# slider_pot_v0_1.net
KiCad netlist of a schematic drawn in EAGLE
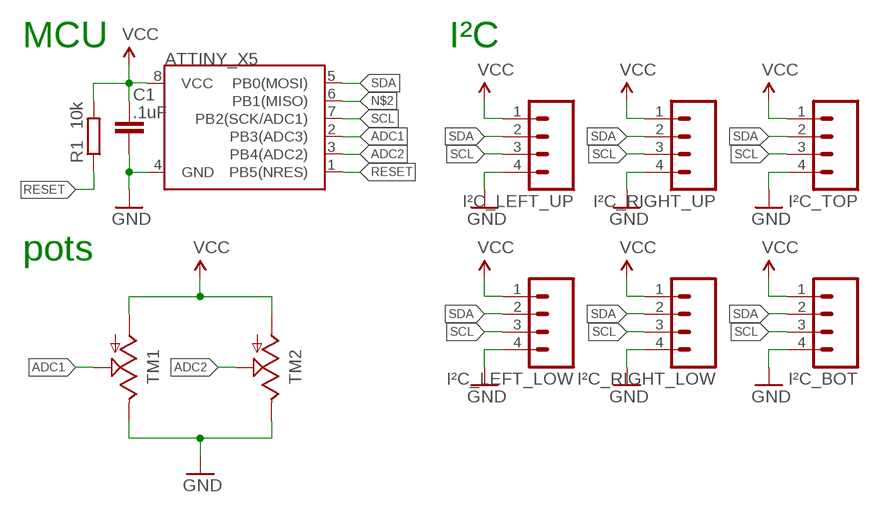
[diagram p0: schematic, sheet 1]

(export (version "E")
  (design (tool "Eeschema 10.0.6"))
  (components
    (comp (ref "ATTINY_X5")
      (value "ATTINY45TINY45-20-SMT")
      (footprint "eagle-import:SO08-EIAJ")
      (libsource (lib "eagle-import") (part "ATTINY45TINY45-20-SMT"))
    )
    (comp (ref "C1")
      (value ".1uF")
      (footprint "eagle-import:C805")
      (libsource (lib "eagle-import") (part "CAPACITOR_NPOL-0805"))
    )
    (comp (ref "I²C_BOT")
      (value "M04PTH")
      (footprint "eagle-import:1X04")
      (libsource (lib "eagle-import") (part "M04PTH"))
    )
    (comp (ref "I²C_LEFT_LOW")
      (value "M04PTH")
      (footprint "eagle-import:1X04")
      (libsource (lib "eagle-import") (part "M04PTH"))
    )
    (comp (ref "I²C_LEFT_UP")
      (value "M04PTH")
      (footprint "eagle-import:1X04")
      (libsource (lib "eagle-import") (part "M04PTH"))
    )
    (comp (ref "I²C_RIGHT_LOW")
      (value "M04PTH")
      (footprint "eagle-import:1X04")
      (libsource (lib "eagle-import") (part "M04PTH"))
    )
    (comp (ref "I²C_RIGHT_UP")
      (value "M04PTH")
      (footprint "eagle-import:1X04")
      (libsource (lib "eagle-import") (part "M04PTH"))
    )
    (comp (ref "I²C_TOP")
      (value "M04PTH")
      (footprint "eagle-import:1X04")
      (libsource (lib "eagle-import") (part "M04PTH"))
    )
    (comp (ref "R1")
      (value "10k")
      (footprint "eagle-import:R805")
      (libsource (lib "eagle-import") (part "RESISTOR-0805R805"))
    )
    (comp (ref "TM1")
      (value "TRIMSLIDE75")
      (footprint "eagle-import:SLIDEPOT-75")
      (libsource (lib "eagle-import") (part "TRIMSLIDE75"))
    )
    (comp (ref "TM2")
      (value "TRIMSLIDE75")
      (footprint "eagle-import:SLIDEPOT-75")
      (libsource (lib "eagle-import") (part "TRIMSLIDE75"))
    )
  )
  (nets
    (net (code "1") (name "ADC1") (class "Default")
      (node (ref "ATTINY_X5") (pin "2") (pinfunction "PB3(ADC3)_2") (pintype "bidirectional"))
      (node (ref "TM1") (pin "WIPER") (pinfunction "WIPER_WIPER") (pintype "passive"))
    )
    (net (code "2") (name "ADC2") (class "Default")
      (node (ref "ATTINY_X5") (pin "3") (pinfunction "PB4(ADC2)_3") (pintype "bidirectional"))
      (node (ref "TM2") (pin "WIPER") (pinfunction "WIPER_WIPER") (pintype "passive"))
    )
    (net (code "3") (name "GND") (class "Default")
      (node (ref "ATTINY_X5") (pin "4") (pinfunction "GND_4") (pintype "bidirectional"))
      (node (ref "C1") (pin "2") (pinfunction "2_2") (pintype "passive"))
      (node (ref "I²C_BOT") (pin "4") (pinfunction "4_4") (pintype "passive"))
      (node (ref "I²C_LEFT_LOW") (pin "4") (pinfunction "4_4") (pintype "passive"))
      (node (ref "I²C_LEFT_UP") (pin "4") (pinfunction "4_4") (pintype "passive"))
      (node (ref "I²C_RIGHT_LOW") (pin "4") (pinfunction "4_4") (pintype "passive"))
      (node (ref "I²C_RIGHT_UP") (pin "4") (pinfunction "4_4") (pintype "passive"))
      (node (ref "I²C_TOP") (pin "4") (pinfunction "4_4") (pintype "passive"))
      (node (ref "TM1") (pin "B") (pinfunction "B_B") (pintype "passive"))
      (node (ref "TM2") (pin "B") (pinfunction "B_B") (pintype "passive"))
    )
    (net (code "4") (name "N$2") (class "Default")
      (node (ref "ATTINY_X5") (pin "6") (pinfunction "PB1(MISO)_6") (pintype "bidirectional"))
    )
    (net (code "5") (name "RESET") (class "Default")
      (node (ref "ATTINY_X5") (pin "1") (pinfunction "PB5(NRES)_1") (pintype "bidirectional"))
      (node (ref "R1") (pin "1") (pinfunction "1_1") (pintype "passive"))
    )
    (net (code "6") (name "SCL") (class "Default")
      (node (ref "ATTINY_X5") (pin "7") (pinfunction "PB2(SCK/ADC1)_7") (pintype "bidirectional"))
      (node (ref "I²C_BOT") (pin "3") (pinfunction "3_3") (pintype "passive"))
      (node (ref "I²C_LEFT_LOW") (pin "3") (pinfunction "3_3") (pintype "passive"))
      (node (ref "I²C_LEFT_UP") (pin "3") (pinfunction "3_3") (pintype "passive"))
      (node (ref "I²C_RIGHT_LOW") (pin "3") (pinfunction "3_3") (pintype "passive"))
      (node (ref "I²C_RIGHT_UP") (pin "3") (pinfunction "3_3") (pintype "passive"))
      (node (ref "I²C_TOP") (pin "3") (pinfunction "3_3") (pintype "passive"))
    )
    (net (code "7") (name "SDA") (class "Default")
      (node (ref "ATTINY_X5") (pin "5") (pinfunction "PB0(MOSI)_5") (pintype "bidirectional"))
      (node (ref "I²C_BOT") (pin "2") (pinfunction "2_2") (pintype "passive"))
      (node (ref "I²C_LEFT_LOW") (pin "2") (pinfunction "2_2") (pintype "passive"))
      (node (ref "I²C_LEFT_UP") (pin "2") (pinfunction "2_2") (pintype "passive"))
      (node (ref "I²C_RIGHT_LOW") (pin "2") (pinfunction "2_2") (pintype "passive"))
      (node (ref "I²C_RIGHT_UP") (pin "2") (pinfunction "2_2") (pintype "passive"))
      (node (ref "I²C_TOP") (pin "2") (pinfunction "2_2") (pintype "passive"))
    )
    (net (code "8") (name "VCC") (class "Default")
      (node (ref "ATTINY_X5") (pin "8") (pinfunction "VCC_8") (pintype "bidirectional"))
      (node (ref "C1") (pin "1") (pinfunction "1_1") (pintype "passive"))
      (node (ref "I²C_BOT") (pin "1") (pinfunction "1_1") (pintype "passive"))
      (node (ref "I²C_LEFT_LOW") (pin "1") (pinfunction "1_1") (pintype "passive"))
      (node (ref "I²C_LEFT_UP") (pin "1") (pinfunction "1_1") (pintype "passive"))
      (node (ref "I²C_RIGHT_LOW") (pin "1") (pinfunction "1_1") (pintype "passive"))
      (node (ref "I²C_RIGHT_UP") (pin "1") (pinfunction "1_1") (pintype "passive"))
      (node (ref "I²C_TOP") (pin "1") (pinfunction "1_1") (pintype "passive"))
      (node (ref "R1") (pin "2") (pinfunction "2_2") (pintype "passive"))
      (node (ref "TM1") (pin "A") (pinfunction "A_A") (pintype "passive"))
      (node (ref "TM2") (pin "A") (pinfunction "A_A") (pintype "passive"))
    )
  )
)
